# Sheet1.net
KiCad netlist of a schematic drawn in Altium Designer
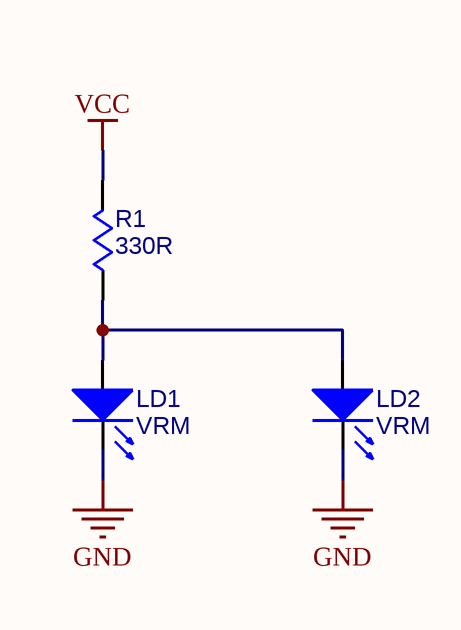
[diagram p0: Sheet1.SchDoc]

(export (version "E")
  (design (tool "Eeschema 10.0.6"))
  (components
    (comp (ref "LD1")
      (value "VRM")
      (footprint "LED3-5-Q-WH")
      (description "DIODO LED VERMELHO, THT, 3MM, QUADRADO")
      (fields (field (name "MANUFACTURER") "SUN LED") (field (name "MPN") "XSMDK43MB"))
      (libsource (lib "Dataprom") (part "D.L.T.VERM.3MM.Q[LED3Q]"))
    )
    (comp (ref "LD2")
      (value "VRM")
      (footprint "LED3-5-Q-WH")
      (description "DIODO LED VERMELHO, THT, 3MM, QUADRADO")
      (fields (field (name "MANUFACTURER") "SUN LED") (field (name "MPN") "XSMDK43MB"))
      (libsource (lib "Dataprom") (part "D.L.T.VERM.3MM.Q[LED3Q]"))
    )
    (comp (ref "R1")
      (value "330R")
      (footprint "AXIAL-0.4")
      (description "RESISTOR THT DE FILME METAL 330R 0,125W 1% (AXIAL 0.4)")
      (libsource (lib "Dataprom") (part "R.T.K.330.1/8W.1Q[AXIAL0.4]"))
    )
  )
  (nets
    (net (code "1") (name "GND") (class "Default")
      (node (ref "LD1") (pin "K") (pinfunction "K_K") (pintype "passive"))
      (node (ref "LD2") (pin "K") (pinfunction "K_K") (pintype "passive"))
    )
    (net (code "2") (name "Net-(LD1-PadA)") (class "Default")
      (node (ref "LD1") (pin "A") (pinfunction "A_A") (pintype "passive"))
      (node (ref "LD2") (pin "A") (pinfunction "A_A") (pintype "passive"))
      (node (ref "R1") (pin "1") (pinfunction "1_1") (pintype "passive"))
    )
    (net (code "3") (name "VCC") (class "Default")
      (node (ref "R1") (pin "2") (pinfunction "2_2") (pintype "passive"))
    )
  )
)
